# cw312ttmp91fw_microcontroller.net
KiCad netlist of a schematic drawn in Altium Designer
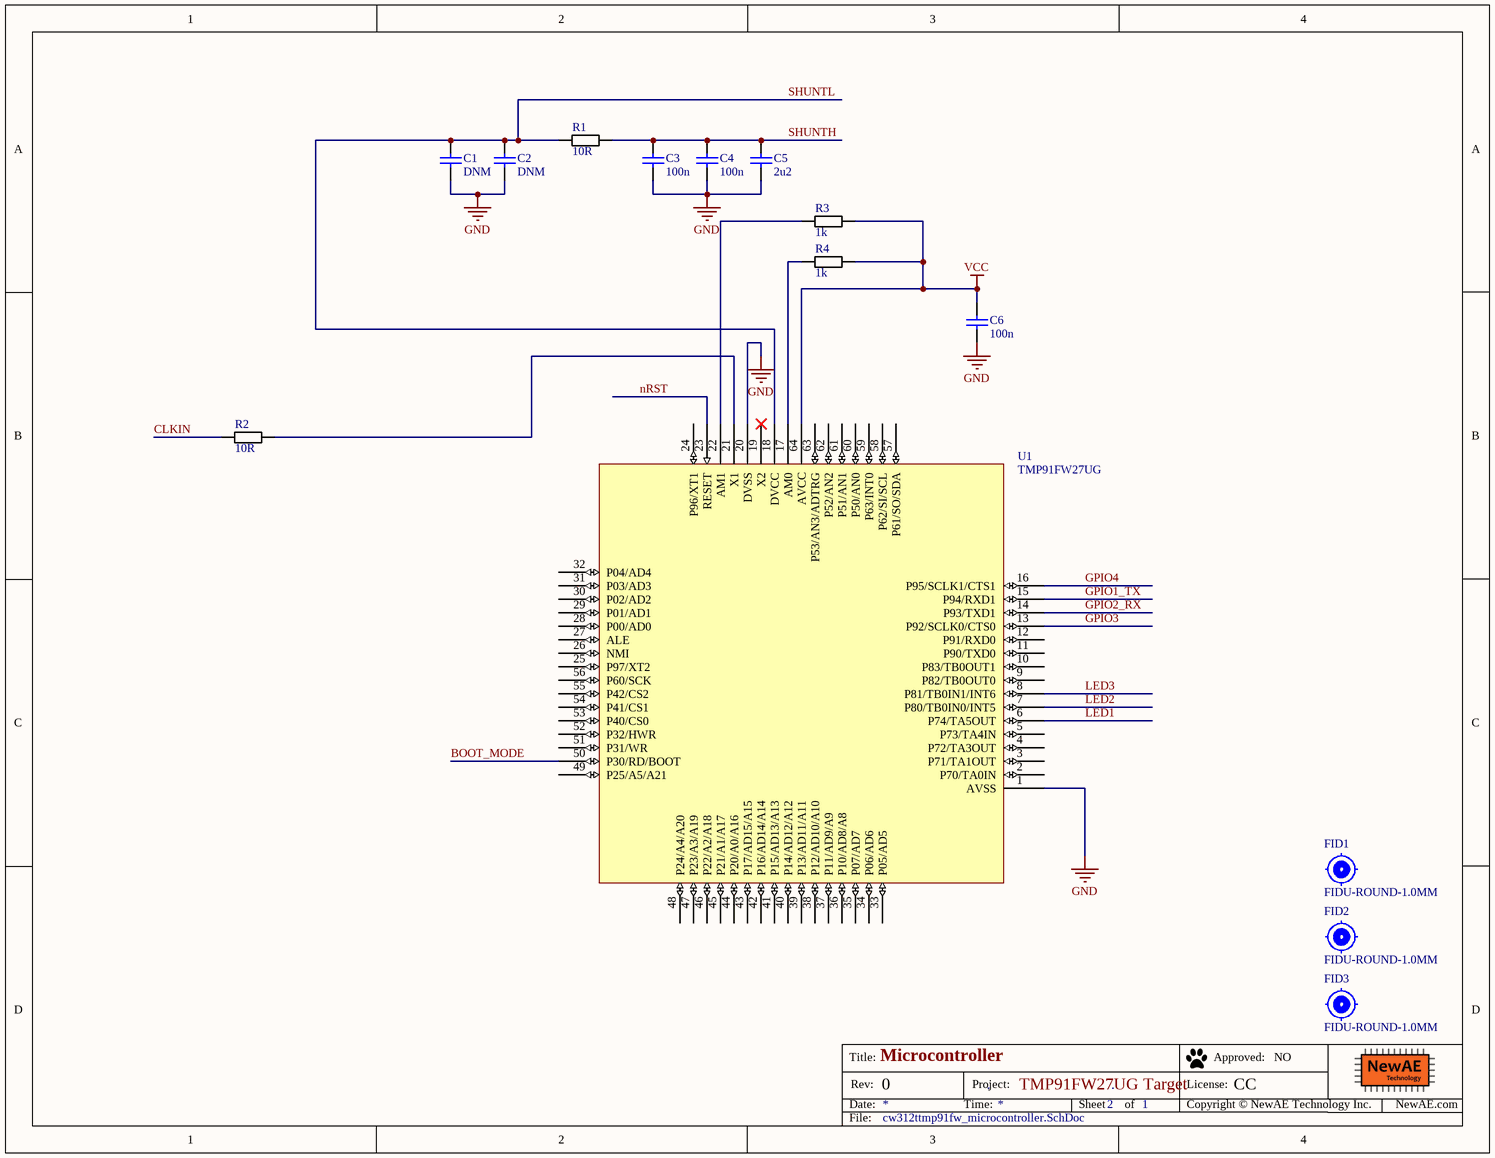
[diagram p0: cw312ttmp91fw_microcontroller.SchDoc]

(export (version "E")
  (design (tool "Eeschema 10.0.6"))
  (components
    (comp (ref "C1")
      (value "DNM")
      (footprint "CAPC0603_M")
      (fields (field (name "PART NUMBER") "CCHIP-100n-0603"))
      (libsource (lib "NewAE_AltiumLib") (part "CAP"))
    )
    (comp (ref "C2")
      (value "DNM")
      (footprint "CAPC0603_M")
      (fields (field (name "PART NUMBER") "CCHIP-100n-0603"))
      (libsource (lib "NewAE_AltiumLib") (part "CAP"))
    )
    (comp (ref "C3")
      (value "100n")
      (footprint "CAPC0603_M")
      (description "100n, 0603")
      (fields (field (name "PART NUMBER") "CCHIP-100n-0603"))
      (libsource (lib "NewAE_AltiumLib") (part "CAP"))
    )
    (comp (ref "C4")
      (value "100n")
      (footprint "CAPC0603_M")
      (description "100n, 0603")
      (fields (field (name "PART NUMBER") "CCHIP-100n-0603"))
      (libsource (lib "NewAE_AltiumLib") (part "CAP"))
    )
    (comp (ref "C5")
      (value "2u2")
      (footprint "CAPC0603_M")
      (description "2u2, 0603")
      (fields (field (name "PART NUMBER") "CCHIP-2u2-0603"))
      (libsource (lib "NewAE_AltiumLib") (part "CAP"))
    )
    (comp (ref "C6")
      (value "100n")
      (footprint "CAPC0603_M")
      (description "100n, 0603")
      (fields (field (name "PART NUMBER") "CCHIP-100n-0603"))
      (libsource (lib "NewAE_AltiumLib") (part "CAP"))
    )
    (comp (ref "FID1")
      (value "FIDU-ROUND-1.0MM")
      (footprint "FIDU-ROUND-1.0mm")
      (description "ROUND FIDUCIAL")
      (libsource (lib "NewAE_AltiumLib") (part "FIDU-ROUND-1.0MM"))
    )
    (comp (ref "FID2")
      (value "FIDU-ROUND-1.0MM")
      (footprint "FIDU-ROUND-1.0mm")
      (description "ROUND FIDUCIAL")
      (libsource (lib "NewAE_AltiumLib") (part "FIDU-ROUND-1.0MM"))
    )
    (comp (ref "FID3")
      (value "FIDU-ROUND-1.0MM")
      (footprint "FIDU-ROUND-1.0mm")
      (description "ROUND FIDUCIAL")
      (libsource (lib "NewAE_AltiumLib") (part "FIDU-ROUND-1.0MM"))
    )
    (comp (ref "R1")
      (value "10R")
      (footprint "RESC1608X55N")
      (description "10R res, 0603, 1%, 1/10W")
      (fields (field (name "PART NUMBER") "RCHIP-10R-0603") (field (name "TOLERANCE") "1%"))
      (libsource (lib "NewAE_AltiumLib") (part "RES-EU"))
    )
    (comp (ref "R2")
      (value "10R")
      (footprint "RESC1608X55N")
      (description "10R res, 0603, 1%, 1/10W")
      (fields (field (name "PART NUMBER") "RCHIP-10R-0603") (field (name "TOLERANCE") "1%"))
      (libsource (lib "NewAE_AltiumLib") (part "RES-EU"))
    )
    (comp (ref "R3")
      (value "1k")
      (footprint "RESC1608X55N")
      (description "1k res, 0603, 1%, 1/10W")
      (fields (field (name "PART NUMBER") "RCHIP-1K-0603") (field (name "TOLERANCE") "1%"))
      (libsource (lib "NewAE_AltiumLib") (part "RES-EU"))
    )
    (comp (ref "R4")
      (value "1k")
      (footprint "RESC1608X55N")
      (description "1k res, 0603, 1%, 1/10W")
      (fields (field (name "PART NUMBER") "RCHIP-1K-0603") (field (name "TOLERANCE") "1%"))
      (libsource (lib "NewAE_AltiumLib") (part "RES-EU"))
    )
    (comp (ref "U1")
      (value "TMP91FW27UG")
      (footprint "TQFP50P1200X1200X120-64N")
      (description "TMP91FW27, 16-bit micro, LQFP64_0.5")
      (libsource (lib "NewAE_AltiumLib") (part "TMP91FW27"))
    )
  )
  (nets
    (net (code "1") (name "/BOOT_MODE") (class "Default")
      (node (ref "U1") (pin "50") (pinfunction "P30/RD/BOOT_50") (pintype "bidirectional"))
    )
    (net (code "2") (name "/CLKIN") (class "Default")
      (node (ref "R2") (pin "1") (pinfunction "1_1") (pintype "passive"))
    )
    (net (code "3") (name "/GPIO1_TX") (class "Default")
      (node (ref "U1") (pin "15") (pinfunction "P94/RXD1_15") (pintype "bidirectional"))
    )
    (net (code "4") (name "/GPIO2_RX") (class "Default")
      (node (ref "U1") (pin "14") (pinfunction "P93/TXD1_14") (pintype "bidirectional"))
    )
    (net (code "5") (name "/GPIO3") (class "Default")
      (node (ref "U1") (pin "13") (pinfunction "P92/SCLK0/CTS0_13") (pintype "bidirectional"))
    )
    (net (code "6") (name "/GPIO4") (class "Default")
      (node (ref "U1") (pin "16") (pinfunction "P95/SCLK1/CTS1_16") (pintype "bidirectional"))
    )
    (net (code "7") (name "/LED1") (class "Default")
      (node (ref "U1") (pin "6") (pinfunction "P74/TA5OUT_6") (pintype "bidirectional"))
    )
    (net (code "8") (name "/LED2") (class "Default")
      (node (ref "U1") (pin "7") (pinfunction "P80/TB0IN0/INT5_7") (pintype "bidirectional"))
    )
    (net (code "9") (name "/LED3") (class "Default")
      (node (ref "U1") (pin "8") (pinfunction "P81/TB0IN1/INT6_8") (pintype "bidirectional"))
    )
    (net (code "10") (name "/SHUNTH") (class "Default")
      (node (ref "C3") (pin "1") (pinfunction "1_1") (pintype "passive"))
      (node (ref "C4") (pin "1") (pinfunction "1_1") (pintype "passive"))
      (node (ref "C5") (pin "1") (pinfunction "1_1") (pintype "passive"))
      (node (ref "R1") (pin "2") (pinfunction "2_2") (pintype "passive"))
    )
    (net (code "11") (name "/SHUNTL") (class "Default")
      (node (ref "C1") (pin "1") (pinfunction "1_1") (pintype "passive"))
      (node (ref "C2") (pin "1") (pinfunction "1_1") (pintype "passive"))
      (node (ref "R1") (pin "1") (pinfunction "1_1") (pintype "passive"))
      (node (ref "U1") (pin "18") (pinfunction "DVCC_18") (pintype "power_in"))
    )
    (net (code "12") (name "/nRST") (class "Default")
      (node (ref "U1") (pin "23") (pinfunction "RESET_23") (pintype "input"))
    )
    (net (code "13") (name "GND") (class "Default")
      (node (ref "C1") (pin "2") (pinfunction "2_2") (pintype "passive"))
      (node (ref "C2") (pin "2") (pinfunction "2_2") (pintype "passive"))
      (node (ref "C3") (pin "2") (pinfunction "2_2") (pintype "passive"))
      (node (ref "C4") (pin "2") (pinfunction "2_2") (pintype "passive"))
      (node (ref "C5") (pin "2") (pinfunction "2_2") (pintype "passive"))
      (node (ref "C6") (pin "2") (pinfunction "2_2") (pintype "passive"))
      (node (ref "U1") (pin "1") (pinfunction "AVSS_1") (pintype "power_in"))
      (node (ref "U1") (pin "20") (pinfunction "DVSS_20") (pintype "power_in"))
    )
    (net (code "14") (name "Net-(U1-AM0)") (class "Default")
      (node (ref "R4") (pin "1") (pinfunction "1_1") (pintype "passive"))
      (node (ref "U1") (pin "17") (pinfunction "AM0_17") (pintype "passive"))
    )
    (net (code "15") (name "Net-(U1-AM1)") (class "Default")
      (node (ref "R3") (pin "1") (pinfunction "1_1") (pintype "passive"))
      (node (ref "U1") (pin "22") (pinfunction "AM1_22") (pintype "passive"))
    )
    (net (code "16") (name "Net-(U1-X1)") (class "Default")
      (node (ref "R2") (pin "2") (pinfunction "2_2") (pintype "passive"))
      (node (ref "U1") (pin "21") (pinfunction "X1_21") (pintype "passive"))
    )
    (net (code "17") (name "VCC") (class "Default")
      (node (ref "C6") (pin "1") (pinfunction "1_1") (pintype "passive"))
      (node (ref "R3") (pin "2") (pinfunction "2_2") (pintype "passive"))
      (node (ref "R4") (pin "2") (pinfunction "2_2") (pintype "passive"))
      (node (ref "U1") (pin "64") (pinfunction "AVCC_64") (pintype "passive"))
    )
    (net (code "18") (name "unconnected-(U1-ALE-Pad27)") (class "Default")
      (node (ref "U1") (pin "27") (pinfunction "ALE_27") (pintype "bidirectional"))
    )
    (net (code "19") (name "unconnected-(U1-NMI-Pad26)") (class "Default")
      (node (ref "U1") (pin "26") (pinfunction "NMI_26") (pintype "bidirectional"))
    )
    (net (code "20") (name "unconnected-(U1-P00{slash}AD0-Pad28)") (class "Default")
      (node (ref "U1") (pin "28") (pinfunction "P00/AD0_28") (pintype "bidirectional"))
    )
    (net (code "21") (name "unconnected-(U1-P01{slash}AD1-Pad29)") (class "Default")
      (node (ref "U1") (pin "29") (pinfunction "P01/AD1_29") (pintype "bidirectional"))
    )
    (net (code "22") (name "unconnected-(U1-P02{slash}AD2-Pad30)") (class "Default")
      (node (ref "U1") (pin "30") (pinfunction "P02/AD2_30") (pintype "bidirectional"))
    )
    (net (code "23") (name "unconnected-(U1-P03{slash}AD3-Pad31)") (class "Default")
      (node (ref "U1") (pin "31") (pinfunction "P03/AD3_31") (pintype "bidirectional"))
    )
    (net (code "24") (name "unconnected-(U1-P04{slash}AD4-Pad32)") (class "Default")
      (node (ref "U1") (pin "32") (pinfunction "P04/AD4_32") (pintype "bidirectional"))
    )
    (net (code "25") (name "unconnected-(U1-P05{slash}AD5-Pad33)") (class "Default")
      (node (ref "U1") (pin "33") (pinfunction "P05/AD5_33") (pintype "bidirectional"))
    )
    (net (code "26") (name "unconnected-(U1-P06{slash}AD6-Pad34)") (class "Default")
      (node (ref "U1") (pin "34") (pinfunction "P06/AD6_34") (pintype "bidirectional"))
    )
    (net (code "27") (name "unconnected-(U1-P07{slash}AD7-Pad35)") (class "Default")
      (node (ref "U1") (pin "35") (pinfunction "P07/AD7_35") (pintype "bidirectional"))
    )
    (net (code "28") (name "unconnected-(U1-P10{slash}AD8{slash}A8-Pad36)") (class "Default")
      (node (ref "U1") (pin "36") (pinfunction "P10/AD8/A8_36") (pintype "bidirectional"))
    )
    (net (code "29") (name "unconnected-(U1-P11{slash}AD9{slash}A9-Pad37)") (class "Default")
      (node (ref "U1") (pin "37") (pinfunction "P11/AD9/A9_37") (pintype "bidirectional"))
    )
    (net (code "30") (name "unconnected-(U1-P12{slash}AD10{slash}A10-Pad38)") (class "Default")
      (node (ref "U1") (pin "38") (pinfunction "P12/AD10/A10_38") (pintype "bidirectional"))
    )
    (net (code "31") (name "unconnected-(U1-P13{slash}AD11{slash}A11-Pad39)") (class "Default")
      (node (ref "U1") (pin "39") (pinfunction "P13/AD11/A11_39") (pintype "bidirectional"))
    )
    (net (code "32") (name "unconnected-(U1-P14{slash}AD12{slash}A12-Pad40)") (class "Default")
      (node (ref "U1") (pin "40") (pinfunction "P14/AD12/A12_40") (pintype "bidirectional"))
    )
    (net (code "33") (name "unconnected-(U1-P15{slash}AD13{slash}A13-Pad41)") (class "Default")
      (node (ref "U1") (pin "41") (pinfunction "P15/AD13/A13_41") (pintype "bidirectional"))
    )
    (net (code "34") (name "unconnected-(U1-P16{slash}AD14{slash}A14-Pad42)") (class "Default")
      (node (ref "U1") (pin "42") (pinfunction "P16/AD14/A14_42") (pintype "bidirectional"))
    )
    (net (code "35") (name "unconnected-(U1-P17{slash}AD15{slash}A15-Pad43)") (class "Default")
      (node (ref "U1") (pin "43") (pinfunction "P17/AD15/A15_43") (pintype "bidirectional"))
    )
    (net (code "36") (name "unconnected-(U1-P20{slash}A0{slash}A16-Pad44)") (class "Default")
      (node (ref "U1") (pin "44") (pinfunction "P20/A0/A16_44") (pintype "bidirectional"))
    )
    (net (code "37") (name "unconnected-(U1-P21{slash}A1{slash}A17-Pad45)") (class "Default")
      (node (ref "U1") (pin "45") (pinfunction "P21/A1/A17_45") (pintype "bidirectional"))
    )
    (net (code "38") (name "unconnected-(U1-P22{slash}A2{slash}A18-Pad46)") (class "Default")
      (node (ref "U1") (pin "46") (pinfunction "P22/A2/A18_46") (pintype "bidirectional"))
    )
    (net (code "39") (name "unconnected-(U1-P23{slash}A3{slash}A19-Pad47)") (class "Default")
      (node (ref "U1") (pin "47") (pinfunction "P23/A3/A19_47") (pintype "bidirectional"))
    )
    (net (code "40") (name "unconnected-(U1-P24{slash}A4{slash}A20-Pad48)") (class "Default")
      (node (ref "U1") (pin "48") (pinfunction "P24/A4/A20_48") (pintype "bidirectional"))
    )
    (net (code "41") (name "unconnected-(U1-P25{slash}A5{slash}A21-Pad49)") (class "Default")
      (node (ref "U1") (pin "49") (pinfunction "P25/A5/A21_49") (pintype "bidirectional"))
    )
    (net (code "42") (name "unconnected-(U1-P31{slash}WR-Pad51)") (class "Default")
      (node (ref "U1") (pin "51") (pinfunction "P31/WR_51") (pintype "bidirectional"))
    )
    (net (code "43") (name "unconnected-(U1-P32{slash}HWR-Pad52)") (class "Default")
      (node (ref "U1") (pin "52") (pinfunction "P32/HWR_52") (pintype "bidirectional"))
    )
    (net (code "44") (name "unconnected-(U1-P40{slash}CS0-Pad53)") (class "Default")
      (node (ref "U1") (pin "53") (pinfunction "P40/CS0_53") (pintype "bidirectional"))
    )
    (net (code "45") (name "unconnected-(U1-P41{slash}CS1-Pad54)") (class "Default")
      (node (ref "U1") (pin "54") (pinfunction "P41/CS1_54") (pintype "bidirectional"))
    )
    (net (code "46") (name "unconnected-(U1-P42{slash}CS2-Pad55)") (class "Default")
      (node (ref "U1") (pin "55") (pinfunction "P42/CS2_55") (pintype "bidirectional"))
    )
    (net (code "47") (name "unconnected-(U1-P50{slash}AN0-Pad60)") (class "Default")
      (node (ref "U1") (pin "60") (pinfunction "P50/AN0_60") (pintype "bidirectional"))
    )
    (net (code "48") (name "unconnected-(U1-P51{slash}AN1-Pad61)") (class "Default")
      (node (ref "U1") (pin "61") (pinfunction "P51/AN1_61") (pintype "bidirectional"))
    )
    (net (code "49") (name "unconnected-(U1-P52{slash}AN2-Pad62)") (class "Default")
      (node (ref "U1") (pin "62") (pinfunction "P52/AN2_62") (pintype "bidirectional"))
    )
    (net (code "50") (name "unconnected-(U1-P53{slash}AN3{slash}ADTRG-Pad63)") (class "Default")
      (node (ref "U1") (pin "63") (pinfunction "P53/AN3/ADTRG_63") (pintype "bidirectional"))
    )
    (net (code "51") (name "unconnected-(U1-P60{slash}SCK-Pad56)") (class "Default")
      (node (ref "U1") (pin "56") (pinfunction "P60/SCK_56") (pintype "bidirectional"))
    )
    (net (code "52") (name "unconnected-(U1-P61{slash}SO{slash}SDA-Pad57)") (class "Default")
      (node (ref "U1") (pin "57") (pinfunction "P61/SO/SDA_57") (pintype "bidirectional"))
    )
    (net (code "53") (name "unconnected-(U1-P62{slash}SI{slash}SCL-Pad58)") (class "Default")
      (node (ref "U1") (pin "58") (pinfunction "P62/SI/SCL_58") (pintype "bidirectional"))
    )
    (net (code "54") (name "unconnected-(U1-P63{slash}INT0-Pad59)") (class "Default")
      (node (ref "U1") (pin "59") (pinfunction "P63/INT0_59") (pintype "bidirectional"))
    )
    (net (code "55") (name "unconnected-(U1-P70{slash}TA0IN-Pad2)") (class "Default")
      (node (ref "U1") (pin "2") (pinfunction "P70/TA0IN_2") (pintype "bidirectional"))
    )
    (net (code "56") (name "unconnected-(U1-P71{slash}TA1OUT-Pad3)") (class "Default")
      (node (ref "U1") (pin "3") (pinfunction "P71/TA1OUT_3") (pintype "bidirectional"))
    )
    (net (code "57") (name "unconnected-(U1-P72{slash}TA3OUT-Pad4)") (class "Default")
      (node (ref "U1") (pin "4") (pinfunction "P72/TA3OUT_4") (pintype "bidirectional"))
    )
    (net (code "58") (name "unconnected-(U1-P73{slash}TA4IN-Pad5)") (class "Default")
      (node (ref "U1") (pin "5") (pinfunction "P73/TA4IN_5") (pintype "bidirectional"))
    )
    (net (code "59") (name "unconnected-(U1-P82{slash}TB0OUT0-Pad9)") (class "Default")
      (node (ref "U1") (pin "9") (pinfunction "P82/TB0OUT0_9") (pintype "bidirectional"))
    )
    (net (code "60") (name "unconnected-(U1-P83{slash}TB0OUT1-Pad10)") (class "Default")
      (node (ref "U1") (pin "10") (pinfunction "P83/TB0OUT1_10") (pintype "bidirectional"))
    )
    (net (code "61") (name "unconnected-(U1-P90{slash}TXD0-Pad11)") (class "Default")
      (node (ref "U1") (pin "11") (pinfunction "P90/TXD0_11") (pintype "bidirectional"))
    )
    (net (code "62") (name "unconnected-(U1-P91{slash}RXD0-Pad12)") (class "Default")
      (node (ref "U1") (pin "12") (pinfunction "P91/RXD0_12") (pintype "bidirectional"))
    )
    (net (code "63") (name "unconnected-(U1-P96{slash}XT1-Pad24)") (class "Default")
      (node (ref "U1") (pin "24") (pinfunction "P96/XT1_24") (pintype "bidirectional"))
    )
    (net (code "64") (name "unconnected-(U1-P97{slash}XT2-Pad25)") (class "Default")
      (node (ref "U1") (pin "25") (pinfunction "P97/XT2_25") (pintype "bidirectional"))
    )
    (net (code "65") (name "unconnected-(U1-X2-Pad19)") (class "Default")
      (node (ref "U1") (pin "19") (pinfunction "X2_19") (pintype "passive+no_connect"))
    )
  )
)
